# Power_Board_3790.net
KiCad netlist of a schematic drawn in Altium Designer
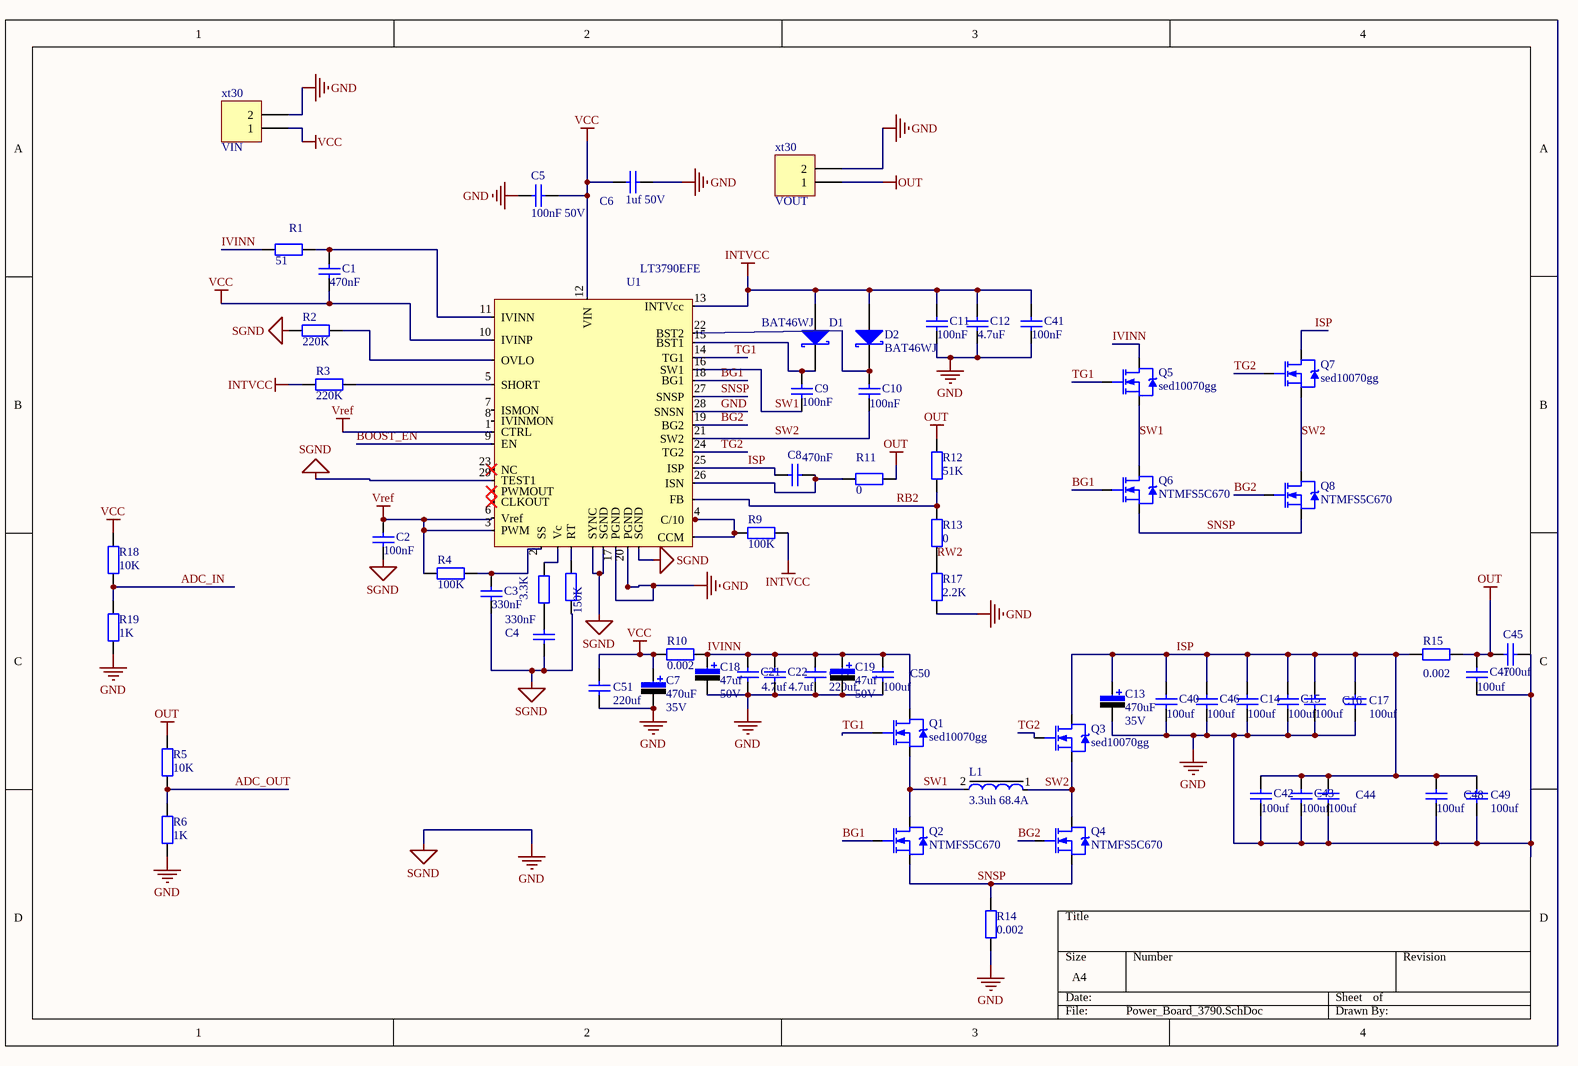
[diagram p0: Power_Board_3790.SchDoc]

(export (version "E")
  (design (tool "Eeschema 10.0.6"))
  (components
    (comp (ref "C1")
      (value "470nF")
      (footprint "c0402")
      (description "无极性电容")
      (fields (field (name "PUBLISHER") "Altium Limited"))
      (libsource (lib "Fszhang") (part "Cap"))
    )
    (comp (ref "C2")
      (value "100nF")
      (footprint "c0402")
      (description "无极性电容")
      (fields (field (name "PUBLISHER") "Altium Limited"))
      (libsource (lib "Fszhang") (part "Cap"))
    )
    (comp (ref "C3")
      (value "330nF")
      (footprint "c0402")
      (description "无极性电容")
      (fields (field (name "PUBLISHER") "Altium Limited"))
      (libsource (lib "Fszhang") (part "Cap"))
    )
    (comp (ref "C4")
      (value "330nF")
      (footprint "c0402")
      (description "无极性电容")
      (fields (field (name "PUBLISHER") "Altium Limited"))
      (libsource (lib "Fszhang") (part "Cap"))
    )
    (comp (ref "C5")
      (value "100nF 50V")
      (footprint "c0402")
      (description "无极性电容")
      (fields (field (name "PUBLISHER") "Altium Limited"))
      (libsource (lib "Fszhang") (part "Cap"))
    )
    (comp (ref "C6")
      (value "1uf 50V")
      (footprint "0805-2")
      (description "无极性电容")
      (fields (field (name "PUBLISHER") "Altium Limited"))
      (libsource (lib "Fszhang") (part "Cap"))
    )
    (comp (ref "C7")
      (value "470uF")
      (footprint "C10X10")
      (description "极性电解电容")
      (fields
        (field (name "VOL") "35V")
        (field (name "Comment") "470uF 35v")
        (field (name "PUBLISHER") "Altium Limited")
      )
      (libsource (lib "Fszhang") (part "Cap Pol"))
    )
    (comp (ref "C8")
      (value "470nF")
      (footprint "c0402")
      (description "无极性电容")
      (fields (field (name "Comment") "470nf") (field (name "PUBLISHER") "Altium Limited"))
      (libsource (lib "Fszhang") (part "Cap"))
    )
    (comp (ref "C9")
      (value "100nF")
      (footprint "c0402")
      (description "无极性电容")
      (fields (field (name "PUBLISHER") "Altium Limited"))
      (libsource (lib "Fszhang") (part "Cap"))
    )
    (comp (ref "C10")
      (value "100nF")
      (footprint "c0402")
      (description "无极性电容")
      (fields (field (name "PUBLISHER") "Altium Limited"))
      (libsource (lib "Fszhang") (part "Cap"))
    )
    (comp (ref "C11")
      (value "100nF")
      (footprint "c0402")
      (description "无极性电容")
      (fields (field (name "PUBLISHER") "Altium Limited"))
      (libsource (lib "Fszhang") (part "Cap"))
    )
    (comp (ref "C12")
      (value "4.7uF")
      (footprint "c0402")
      (description "无极性电容")
      (fields (field (name "PUBLISHER") "Altium Limited"))
      (libsource (lib "Fszhang") (part "Cap"))
    )
    (comp (ref "C13")
      (value "470uF")
      (footprint "C10X10")
      (description "极性电解电容")
      (fields
        (field (name "VOL") "35V")
        (field (name "Comment") "470uf 35V")
        (field (name "PUBLISHER") "Altium Limited")
      )
      (libsource (lib "Fszhang") (part "Cap Pol"))
    )
    (comp (ref "C14")
      (value "100uf")
      (footprint "1210")
      (description "无极性电容")
      (fields (field (name "PUBLISHER") "Altium Limited"))
      (libsource (lib "Fszhang") (part "Cap"))
    )
    (comp (ref "C15")
      (value "100uf")
      (footprint "1210")
      (description "无极性电容")
      (fields (field (name "PUBLISHER") "Altium Limited"))
      (libsource (lib "Fszhang") (part "Cap"))
    )
    (comp (ref "C16")
      (value "100uf")
      (footprint "1210")
      (description "无极性电容")
      (fields (field (name "PUBLISHER") "Altium Limited"))
      (libsource (lib "Fszhang") (part "Cap"))
    )
    (comp (ref "C17")
      (value "100uf")
      (footprint "1210")
      (description "无极性电容")
      (fields (field (name "PUBLISHER") "Altium Limited"))
      (libsource (lib "Fszhang") (part "Cap"))
    )
    (comp (ref "C18")
      (value "47uf")
      (footprint "6.3*7.7MM")
      (description "极性电解电容")
      (fields (field (name "VOL") "50V") (field (name "PUBLISHER") "Altium Limited"))
      (libsource (lib "Fszhang") (part "Cap Pol"))
    )
    (comp (ref "C19")
      (value "47uf")
      (footprint "6.3*7.7MM")
      (description "极性电解电容")
      (fields (field (name "VOL") "50V") (field (name "PUBLISHER") "Altium Limited"))
      (libsource (lib "Fszhang") (part "Cap Pol"))
    )
    (comp (ref "C21")
      (value "4.7uf")
      (footprint "1210")
      (description "无极性电容")
      (fields (field (name "PUBLISHER") "Altium Limited"))
      (libsource (lib "Fszhang") (part "Cap"))
    )
    (comp (ref "C22")
      (value "4.7uf")
      (footprint "1210")
      (description "无极性电容")
      (fields (field (name "PUBLISHER") "Altium Limited"))
      (libsource (lib "Fszhang") (part "Cap"))
    )
    (comp (ref "C39")
      (value "220uf")
      (footprint "1210")
      (description "无极性电容")
      (fields (field (name "PUBLISHER") "Altium Limited"))
      (libsource (lib "Fszhang") (part "Cap"))
    )
    (comp (ref "C40")
      (value "100uf")
      (footprint "1210")
      (description "无极性电容")
      (fields (field (name "PUBLISHER") "Altium Limited"))
      (libsource (lib "Fszhang") (part "Cap"))
    )
    (comp (ref "C41")
      (value "100nF")
      (footprint "c0402")
      (description "无极性电容")
      (fields (field (name "PUBLISHER") "Altium Limited"))
      (libsource (lib "Fszhang") (part "Cap"))
    )
    (comp (ref "C42")
      (value "100uf")
      (footprint "1210")
      (description "无极性电容")
      (fields (field (name "PUBLISHER") "Altium Limited"))
      (libsource (lib "Fszhang") (part "Cap"))
    )
    (comp (ref "C43")
      (value "100uf")
      (footprint "1210")
      (description "无极性电容")
      (fields (field (name "PUBLISHER") "Altium Limited"))
      (libsource (lib "Fszhang") (part "Cap"))
    )
    (comp (ref "C44")
      (value "100uf")
      (footprint "1210")
      (description "无极性电容")
      (fields (field (name "PUBLISHER") "Altium Limited"))
      (libsource (lib "Fszhang") (part "Cap"))
    )
    (comp (ref "C45")
      (value "100uf")
      (footprint "1210")
      (description "无极性电容")
      (fields (field (name "PUBLISHER") "Altium Limited"))
      (libsource (lib "Fszhang") (part "Cap"))
    )
    (comp (ref "C46")
      (value "100uf")
      (footprint "1210")
      (description "无极性电容")
      (fields (field (name "PUBLISHER") "Altium Limited"))
      (libsource (lib "Fszhang") (part "Cap"))
    )
    (comp (ref "C47")
      (value "100uf")
      (footprint "1210")
      (description "无极性电容")
      (fields (field (name "PUBLISHER") "Altium Limited"))
      (libsource (lib "Fszhang") (part "Cap"))
    )
    (comp (ref "C48")
      (value "100uf")
      (footprint "1210")
      (description "无极性电容")
      (fields (field (name "PUBLISHER") "Altium Limited"))
      (libsource (lib "Fszhang") (part "Cap"))
    )
    (comp (ref "C49")
      (value "100uf")
      (footprint "1210")
      (description "无极性电容")
      (fields (field (name "PUBLISHER") "Altium Limited"))
      (libsource (lib "Fszhang") (part "Cap"))
    )
    (comp (ref "C50")
      (value "100uf")
      (footprint "1210")
      (description "无极性电容")
      (fields (field (name "PUBLISHER") "Altium Limited"))
      (libsource (lib "Fszhang") (part "Cap"))
    )
    (comp (ref "C51")
      (value "220uf")
      (footprint "1210")
      (description "无极性电容")
      (fields (field (name "PUBLISHER") "Altium Limited"))
      (libsource (lib "Fszhang") (part "Cap"))
    )
    (comp (ref "D1")
      (value "D-Schottky")
      (footprint "sod323")
      (description "肖特基二极管")
      (fields (field (name "TYPE") "BAT46WJ") (field (name "PUBLISHER") "Altium Limited"))
      (libsource (lib "Fszhang") (part "D-Schottky"))
    )
    (comp (ref "D2")
      (value "D-Schottky")
      (footprint "sod323")
      (description "肖特基二极管")
      (fields (field (name "TYPE") "BAT46WJ") (field (name "PUBLISHER") "Altium Limited"))
      (libsource (lib "Fszhang") (part "D-Schottky"))
    )
    (comp (ref "L1")
      (value "10uH")
      (footprint "SER-2900")
      (description "扁铜线功率电感")
      (fields (field (name "L") "3.3uh 68.4A"))
      (libsource (lib "super_cap") (part "L"))
    )
    (comp (ref "Q1")
      (value "sed10070gg")
      (footprint "pg-tdson-8")
      (description "MOS")
      (fields (field (name "PUBLISHER") "Altium Limited"))
      (libsource (lib "super_cap") (part "NMOS-2"))
    )
    (comp (ref "Q2")
      (value "NTMFS5C670")
      (footprint "pg-tdson-8")
      (description "MOS")
      (fields (field (name "PUBLISHER") "Altium Limited"))
      (libsource (lib "super_cap") (part "NMOS-2"))
    )
    (comp (ref "Q3")
      (value "sed10070gg")
      (footprint "pg-tdson-8")
      (description "MOS")
      (fields (field (name "PUBLISHER") "Altium Limited"))
      (libsource (lib "super_cap") (part "NMOS-2"))
    )
    (comp (ref "Q4")
      (value "NTMFS5C670")
      (footprint "pg-tdson-8")
      (description "MOS")
      (fields (field (name "PUBLISHER") "Altium Limited"))
      (libsource (lib "super_cap") (part "NMOS-2"))
    )
    (comp (ref "Q5")
      (value "sed10070gg")
      (footprint "pg-tdson-8")
      (description "MOS")
      (fields (field (name "PUBLISHER") "Altium Limited"))
      (libsource (lib "super_cap") (part "NMOS-2"))
    )
    (comp (ref "Q6")
      (value "NTMFS5C670")
      (footprint "pg-tdson-8")
      (description "MOS")
      (fields (field (name "PUBLISHER") "Altium Limited"))
      (libsource (lib "super_cap") (part "NMOS-2"))
    )
    (comp (ref "Q7")
      (value "sed10070gg")
      (footprint "pg-tdson-8")
      (description "MOS")
      (fields (field (name "PUBLISHER") "Altium Limited"))
      (libsource (lib "super_cap") (part "NMOS-2"))
    )
    (comp (ref "Q8")
      (value "NTMFS5C670")
      (footprint "pg-tdson-8")
      (description "MOS")
      (fields (field (name "PUBLISHER") "Altium Limited"))
      (libsource (lib "super_cap") (part "NMOS-2"))
    )
    (comp (ref "R1")
      (value "51")
      (footprint "r0402")
      (description "贴片电阻")
      (fields (field (name "PUBLISHER") "Altium Limited"))
      (libsource (lib "") (part "Res1_1"))
    )
    (comp (ref "R2")
      (value "220K")
      (footprint "r0402")
      (description "贴片电阻")
      (fields (field (name "PUBLISHER") "Altium Limited"))
      (libsource (lib "") (part "Res1_1"))
    )
    (comp (ref "R3")
      (value "220K")
      (footprint "r0402")
      (description "贴片电阻")
      (fields (field (name "PUBLISHER") "Altium Limited"))
      (libsource (lib "") (part "Res1_1"))
    )
    (comp (ref "R4")
      (value "100K")
      (footprint "r0402")
      (description "贴片电阻")
      (fields (field (name "PUBLISHER") "Altium Limited"))
      (libsource (lib "") (part "Res1_1"))
    )
    (comp (ref "R5")
      (value "10K")
      (footprint "r0402")
      (description "贴片电阻")
      (fields (field (name "PUBLISHER") "Altium Limited"))
      (libsource (lib "Fszhang") (part "Res1"))
    )
    (comp (ref "R6")
      (value "1K")
      (footprint "r0402")
      (description "贴片电阻")
      (fields (field (name "PUBLISHER") "Altium Limited"))
      (libsource (lib "") (part "Res1_2"))
    )
    (comp (ref "R7")
      (value "3.3K")
      (footprint "r0402")
      (description "贴片电阻")
      (fields (field (name "PUBLISHER") "Altium Limited"))
      (libsource (lib "Fszhang") (part "Res1"))
    )
    (comp (ref "R8")
      (value "150K")
      (footprint "r0402")
      (description "贴片电阻")
      (fields (field (name "PUBLISHER") "Altium Limited"))
      (libsource (lib "Fszhang") (part "Res1"))
    )
    (comp (ref "R9")
      (value "100K")
      (footprint "r0402")
      (description "贴片电阻")
      (fields (field (name "PUBLISHER") "Altium Limited"))
      (libsource (lib "") (part "Res1_1"))
    )
    (comp (ref "R10")
      (value "0.002")
      (footprint "2512")
      (description "贴片电阻")
      (fields (field (name "PUBLISHER") "Altium Limited"))
      (libsource (lib "") (part "Res1_1"))
    )
    (comp (ref "R11")
      (value "0")
      (footprint "r0402")
      (description "贴片电阻")
      (fields (field (name "PUBLISHER") "Altium Limited"))
      (libsource (lib "") (part "Res1_1"))
    )
    (comp (ref "R12")
      (value "51K")
      (footprint "r0402")
      (description "贴片电阻")
      (fields (field (name "PUBLISHER") "Altium Limited"))
      (libsource (lib "Fszhang") (part "Res1"))
    )
    (comp (ref "R13")
      (value "0")
      (footprint "r0402")
      (description "贴片电阻")
      (fields (field (name "PUBLISHER") "Altium Limited"))
      (libsource (lib "") (part "Res1_2"))
    )
    (comp (ref "R14")
      (value "0.002")
      (footprint "2512")
      (description "贴片电阻")
      (fields (field (name "PUBLISHER") "Altium Limited"))
      (libsource (lib "") (part "Res1_2"))
    )
    (comp (ref "R15")
      (value "0.002")
      (footprint "2512")
      (description "贴片电阻")
      (fields (field (name "PUBLISHER") "Altium Limited"))
      (libsource (lib "") (part "Res1_1"))
    )
    (comp (ref "R17")
      (value "2.2K")
      (footprint "r0402")
      (description "贴片电阻")
      (fields (field (name "PUBLISHER") "Altium Limited"))
      (libsource (lib "Fszhang") (part "Res1"))
    )
    (comp (ref "R18")
      (value "10K")
      (footprint "r0402")
      (description "贴片电阻")
      (fields (field (name "PUBLISHER") "Altium Limited"))
      (libsource (lib "Fszhang") (part "Res1"))
    )
    (comp (ref "R19")
      (value "1K")
      (footprint "r0402")
      (description "贴片电阻")
      (fields (field (name "PUBLISHER") "Altium Limited"))
      (libsource (lib "") (part "Res1_2"))
    )
    (comp (ref "U1")
      (value "LT3790EFE")
      (footprint "TSSOP38")
      (description "DC-DC芯片")
      (libsource (lib "super_cap") (part "LT3790"))
    )
    (comp (ref "VIN")
      (value "xt30")
      (footprint "XT30-M")
      (description "接插件")
      (fields (field (name "PUBLISHER") "Altium Limited"))
      (libsource (lib "Fszhang") (part "Header 2"))
    )
    (comp (ref "VOUT")
      (value "xt30")
      (footprint "XT30-M")
      (description "接插件")
      (fields (field (name "PUBLISHER") "Altium Limited"))
      (libsource (lib "Fszhang") (part "Header 2"))
    )
  )
  (nets
    (net (code "1") (name "/ADC_IN") (class "Default")
      (node (ref "R18") (pin "1") (pinfunction "1_1") (pintype "passive"))
      (node (ref "R19") (pin "1") (pinfunction "1_1") (pintype "passive"))
    )
    (net (code "2") (name "/ADC_OUT") (class "Default")
      (node (ref "R5") (pin "1") (pinfunction "1_1") (pintype "passive"))
      (node (ref "R6") (pin "1") (pinfunction "1_1") (pintype "passive"))
    )
    (net (code "3") (name "/BG1") (class "Default")
      (node (ref "Q2") (pin "1") (pinfunction "G_1") (pintype "passive"))
      (node (ref "Q6") (pin "1") (pinfunction "G_1") (pintype "passive"))
      (node (ref "U1") (pin "18") (pinfunction "BG1_18") (pintype "passive"))
    )
    (net (code "4") (name "/BG2") (class "Default")
      (node (ref "Q4") (pin "1") (pinfunction "G_1") (pintype "passive"))
      (node (ref "Q8") (pin "1") (pinfunction "G_1") (pintype "passive"))
      (node (ref "U1") (pin "19") (pinfunction "BG2_19") (pintype "passive"))
    )
    (net (code "5") (name "/BOOST_EN") (class "Default")
      (node (ref "U1") (pin "9") (pinfunction "EN_9") (pintype "passive"))
    )
    (net (code "6") (name "/ISP") (class "Default")
      (node (ref "C13") (pin "1") (pinfunction "1_1") (pintype "passive"))
      (node (ref "C14") (pin "2") (pinfunction "2_2") (pintype "passive"))
      (node (ref "C15") (pin "2") (pinfunction "2_2") (pintype "passive"))
      (node (ref "C16") (pin "2") (pinfunction "2_2") (pintype "passive"))
      (node (ref "C17") (pin "2") (pinfunction "2_2") (pintype "passive"))
      (node (ref "C40") (pin "2") (pinfunction "2_2") (pintype "passive"))
      (node (ref "C42") (pin "2") (pinfunction "2_2") (pintype "passive"))
      (node (ref "C43") (pin "2") (pinfunction "2_2") (pintype "passive"))
      (node (ref "C44") (pin "2") (pinfunction "2_2") (pintype "passive"))
      (node (ref "C46") (pin "2") (pinfunction "2_2") (pintype "passive"))
      (node (ref "C48") (pin "2") (pinfunction "2_2") (pintype "passive"))
      (node (ref "C49") (pin "2") (pinfunction "2_2") (pintype "passive"))
      (node (ref "C8") (pin "2") (pinfunction "2_2") (pintype "passive"))
      (node (ref "Q3") (pin "2") (pinfunction "D_2") (pintype "passive"))
      (node (ref "Q7") (pin "2") (pinfunction "D_2") (pintype "passive"))
      (node (ref "R15") (pin "1") (pinfunction "1_1") (pintype "passive"))
      (node (ref "U1") (pin "25") (pinfunction "ISP_25") (pintype "passive"))
    )
    (net (code "7") (name "/IVINN") (class "Default")
      (node (ref "C18") (pin "1") (pinfunction "1_1") (pintype "passive"))
      (node (ref "C19") (pin "1") (pinfunction "1_1") (pintype "passive"))
      (node (ref "C21") (pin "2") (pinfunction "2_2") (pintype "passive"))
      (node (ref "C22") (pin "2") (pinfunction "2_2") (pintype "passive"))
      (node (ref "C39") (pin "2") (pinfunction "2_2") (pintype "passive"))
      (node (ref "C50") (pin "2") (pinfunction "2_2") (pintype "passive"))
      (node (ref "Q1") (pin "2") (pinfunction "D_2") (pintype "passive"))
      (node (ref "Q5") (pin "2") (pinfunction "D_2") (pintype "passive"))
      (node (ref "R1") (pin "1") (pinfunction "1_1") (pintype "passive"))
      (node (ref "R10") (pin "2") (pinfunction "2_2") (pintype "passive"))
    )
    (net (code "8") (name "/RB2") (class "Default")
      (node (ref "R12") (pin "1") (pinfunction "1_1") (pintype "passive"))
      (node (ref "R13") (pin "1") (pinfunction "1_1") (pintype "passive"))
      (node (ref "U1") (pin "37") (pinfunction "FB_37") (pintype "passive"))
    )
    (net (code "9") (name "/RW2") (class "Default")
      (node (ref "R13") (pin "2") (pinfunction "2_2") (pintype "passive"))
      (node (ref "R17") (pin "2") (pinfunction "2_2") (pintype "passive"))
    )
    (net (code "10") (name "/SNSP") (class "Default")
      (node (ref "Q2") (pin "3") (pinfunction "S_3") (pintype "passive"))
      (node (ref "Q4") (pin "3") (pinfunction "S_3") (pintype "passive"))
      (node (ref "Q6") (pin "3") (pinfunction "S_3") (pintype "passive"))
      (node (ref "Q8") (pin "3") (pinfunction "S_3") (pintype "passive"))
      (node (ref "R14") (pin "1") (pinfunction "1_1") (pintype "passive"))
      (node (ref "U1") (pin "27") (pinfunction "SNSP_27") (pintype "passive"))
    )
    (net (code "11") (name "/SW1") (class "Default")
      (node (ref "C9") (pin "1") (pinfunction "1_1") (pintype "passive"))
      (node (ref "L1") (pin "2") (pinfunction "1_2") (pintype "passive"))
      (node (ref "Q1") (pin "3") (pinfunction "S_3") (pintype "passive"))
      (node (ref "Q2") (pin "2") (pinfunction "D_2") (pintype "passive"))
      (node (ref "Q5") (pin "3") (pinfunction "S_3") (pintype "passive"))
      (node (ref "Q6") (pin "2") (pinfunction "D_2") (pintype "passive"))
      (node (ref "U1") (pin "16") (pinfunction "SW1_16") (pintype "passive"))
    )
    (net (code "12") (name "/SW2") (class "Default")
      (node (ref "C10") (pin "1") (pinfunction "1_1") (pintype "passive"))
      (node (ref "L1") (pin "1") (pinfunction "2_1") (pintype "passive"))
      (node (ref "Q3") (pin "3") (pinfunction "S_3") (pintype "passive"))
      (node (ref "Q4") (pin "2") (pinfunction "D_2") (pintype "passive"))
      (node (ref "Q7") (pin "3") (pinfunction "S_3") (pintype "passive"))
      (node (ref "Q8") (pin "2") (pinfunction "D_2") (pintype "passive"))
      (node (ref "U1") (pin "21") (pinfunction "SW2_21") (pintype "passive"))
    )
    (net (code "13") (name "/TG1") (class "Default")
      (node (ref "Q1") (pin "1") (pinfunction "G_1") (pintype "passive"))
      (node (ref "Q5") (pin "1") (pinfunction "G_1") (pintype "passive"))
      (node (ref "U1") (pin "14") (pinfunction "TG1_14") (pintype "passive"))
    )
    (net (code "14") (name "/TG2") (class "Default")
      (node (ref "Q3") (pin "1") (pinfunction "G_1") (pintype "passive"))
      (node (ref "Q7") (pin "1") (pinfunction "G_1") (pintype "passive"))
      (node (ref "U1") (pin "24") (pinfunction "TG2_24") (pintype "passive"))
    )
    (net (code "15") (name "GND") (class "Default")
      (node (ref "C11") (pin "1") (pinfunction "1_1") (pintype "passive"))
      (node (ref "C12") (pin "1") (pinfunction "1_1") (pintype "passive"))
      (node (ref "C13") (pin "2") (pinfunction "2_2") (pintype "passive"))
      (node (ref "C14") (pin "1") (pinfunction "1_1") (pintype "passive"))
      (node (ref "C15") (pin "1") (pinfunction "1_1") (pintype "passive"))
      (node (ref "C16") (pin "1") (pinfunction "1_1") (pintype "passive"))
      (node (ref "C17") (pin "1") (pinfunction "1_1") (pintype "passive"))
      (node (ref "C18") (pin "2") (pinfunction "2_2") (pintype "passive"))
      (node (ref "C19") (pin "2") (pinfunction "2_2") (pintype "passive"))
      (node (ref "C2") (pin "1") (pinfunction "1_1") (pintype "passive"))
      (node (ref "C21") (pin "1") (pinfunction "1_1") (pintype "passive"))
      (node (ref "C22") (pin "1") (pinfunction "1_1") (pintype "passive"))
      (node (ref "C3") (pin "1") (pinfunction "1_1") (pintype "passive"))
      (node (ref "C39") (pin "1") (pinfunction "1_1") (pintype "passive"))
      (node (ref "C4") (pin "1") (pinfunction "1_1") (pintype "passive"))
      (node (ref "C40") (pin "1") (pinfunction "1_1") (pintype "passive"))
      (node (ref "C41") (pin "1") (pinfunction "1_1") (pintype "passive"))
      (node (ref "C42") (pin "1") (pinfunction "1_1") (pintype "passive"))
      (node (ref "C43") (pin "1") (pinfunction "1_1") (pintype "passive"))
      (node (ref "C44") (pin "1") (pinfunction "1_1") (pintype "passive"))
      (node (ref "C45") (pin "2") (pinfunction "2_2") (pintype "passive"))
      (node (ref "C46") (pin "1") (pinfunction "1_1") (pintype "passive"))
      (node (ref "C47") (pin "1") (pinfunction "1_1") (pintype "passive"))
      (node (ref "C48") (pin "1") (pinfunction "1_1") (pintype "passive"))
      (node (ref "C49") (pin "1") (pinfunction "1_1") (pintype "passive"))
      (node (ref "C5") (pin "1") (pinfunction "1_1") (pintype "passive"))
      (node (ref "C50") (pin "1") (pinfunction "1_1") (pintype "passive"))
      (node (ref "C51") (pin "1") (pinfunction "1_1") (pintype "passive"))
      (node (ref "C6") (pin "1") (pinfunction "1_1") (pintype "passive"))
      (node (ref "C7") (pin "2") (pinfunction "2_2") (pintype "passive"))
      (node (ref "R14") (pin "2") (pinfunction "2_2") (pintype "passive"))
      (node (ref "R17") (pin "1") (pinfunction "1_1") (pintype "passive"))
      (node (ref "R19") (pin "2") (pinfunction "2_2") (pintype "passive"))
      (node (ref "R2") (pin "1") (pinfunction "1_1") (pintype "passive"))
      (node (ref "R6") (pin "2") (pinfunction "2_2") (pintype "passive"))
      (node (ref "R8") (pin "1") (pinfunction "1_1") (pintype "passive"))
      (node (ref "U1") (pin "17") (pinfunction "PGND_17") (pintype "passive"))
      (node (ref "U1") (pin "20") (pinfunction "PGND_20") (pintype "passive"))
      (node (ref "U1") (pin "28") (pinfunction "SNSN_28") (pintype "passive"))
      (node (ref "U1") (pin "29") (pinfunction "TEST1_29") (pintype "passive"))
      (node (ref "U1") (pin "30") (pinfunction "SGND_30") (pintype "passive"))
      (node (ref "U1") (pin "34") (pinfunction "SYNC_34") (pintype "passive"))
      (node (ref "U1") (pin "39") (pinfunction "SGND_39") (pintype "passive"))
      (node (ref "VIN") (pin "2") (pinfunction "2_2") (pintype "passive"))
      (node (ref "VOUT") (pin "2") (pinfunction "2_2") (pintype "passive"))
    )
    (net (code "16") (name "INTVCC") (class "Default")
      (node (ref "C11") (pin "2") (pinfunction "2_2") (pintype "passive"))
      (node (ref "C12") (pin "2") (pinfunction "2_2") (pintype "passive"))
      (node (ref "C41") (pin "2") (pinfunction "2_2") (pintype "passive"))
      (node (ref "D1") (pin "1") (pinfunction "A_1") (pintype "passive"))
      (node (ref "D2") (pin "1") (pinfunction "A_1") (pintype "passive"))
      (node (ref "R3") (pin "1") (pinfunction "1_1") (pintype "passive"))
      (node (ref "R9") (pin "2") (pinfunction "2_2") (pintype "passive"))
      (node (ref "U1") (pin "13") (pinfunction "INTVcc_13") (pintype "passive"))
    )
    (net (code "17") (name "Net-(C4-Pad2)") (class "Default")
      (node (ref "C4") (pin "2") (pinfunction "2_2") (pintype "passive"))
      (node (ref "R7") (pin "1") (pinfunction "1_1") (pintype "passive"))
    )
    (net (code "18") (name "Net-(D1-K)") (class "Default")
      (node (ref "C9") (pin "2") (pinfunction "2_2") (pintype "passive"))
      (node (ref "D1") (pin "2") (pinfunction "K_2") (pintype "passive"))
      (node (ref "U1") (pin "15") (pinfunction "BST1_15") (pintype "passive"))
    )
    (net (code "19") (name "Net-(D2-K)") (class "Default")
      (node (ref "C10") (pin "2") (pinfunction "2_2") (pintype "passive"))
      (node (ref "D2") (pin "2") (pinfunction "K_2") (pintype "passive"))
      (node (ref "U1") (pin "22") (pinfunction "BST2_22") (pintype "passive"))
    )
    (net (code "20") (name "Net-(U1-CCM)") (class "Default")
      (node (ref "R9") (pin "1") (pinfunction "1_1") (pintype "passive"))
      (node (ref "U1") (pin "32") (pinfunction "CCM_32") (pintype "passive"))
      (node (ref "U1") (pin "4") (pinfunction "C/10_4") (pintype "passive"))
    )
    (net (code "21") (name "Net-(U1-ISN)") (class "Default")
      (node (ref "C8") (pin "1") (pinfunction "1_1") (pintype "passive"))
      (node (ref "R11") (pin "1") (pinfunction "1_1") (pintype "passive"))
      (node (ref "U1") (pin "26") (pinfunction "ISN_26") (pintype "passive"))
    )
    (net (code "22") (name "Net-(U1-IVINN)") (class "Default")
      (node (ref "C1") (pin "2") (pinfunction "2_2") (pintype "passive"))
      (node (ref "R1") (pin "2") (pinfunction "2_2") (pintype "passive"))
      (node (ref "U1") (pin "11") (pinfunction "IVINN_11") (pintype "passive"))
    )
    (net (code "23") (name "Net-(U1-OVLO)") (class "Default")
      (node (ref "R2") (pin "2") (pinfunction "2_2") (pintype "passive"))
      (node (ref "U1") (pin "38") (pinfunction "OVLO_38") (pintype "passive"))
    )
    (net (code "24") (name "Net-(U1-RT)") (class "Default")
      (node (ref "R8") (pin "2") (pinfunction "2_2") (pintype "passive"))
      (node (ref "U1") (pin "35") (pinfunction "RT_35") (pintype "passive"))
    )
    (net (code "25") (name "Net-(U1-SHORT)") (class "Default")
      (node (ref "R3") (pin "2") (pinfunction "2_2") (pintype "passive"))
      (node (ref "U1") (pin "5") (pinfunction "SHORT_5") (pintype "passive"))
    )
    (net (code "26") (name "Net-(U1-SS)") (class "Default")
      (node (ref "C3") (pin "2") (pinfunction "2_2") (pintype "passive"))
      (node (ref "R4") (pin "2") (pinfunction "2_2") (pintype "passive"))
      (node (ref "U1") (pin "2") (pinfunction "SS_2") (pintype "passive"))
    )
    (net (code "27") (name "Net-(U1-Vc)") (class "Default")
      (node (ref "R7") (pin "2") (pinfunction "2_2") (pintype "passive"))
      (node (ref "U1") (pin "36") (pinfunction "Vc_36") (pintype "passive"))
    )
    (net (code "28") (name "OUT") (class "Default")
      (node (ref "C45") (pin "1") (pinfunction "1_1") (pintype "passive"))
      (node (ref "C47") (pin "2") (pinfunction "2_2") (pintype "passive"))
      (node (ref "R11") (pin "2") (pinfunction "2_2") (pintype "passive"))
      (node (ref "R12") (pin "2") (pinfunction "2_2") (pintype "passive"))
      (node (ref "R15") (pin "2") (pinfunction "2_2") (pintype "passive"))
      (node (ref "R5") (pin "2") (pinfunction "2_2") (pintype "passive"))
      (node (ref "VOUT") (pin "1") (pinfunction "1_1") (pintype "passive"))
    )
    (net (code "29") (name "VCC") (class "Default")
      (node (ref "C1") (pin "1") (pinfunction "1_1") (pintype "passive"))
      (node (ref "C5") (pin "2") (pinfunction "2_2") (pintype "passive"))
      (node (ref "C51") (pin "2") (pinfunction "2_2") (pintype "passive"))
      (node (ref "C6") (pin "2") (pinfunction "2_2") (pintype "passive"))
      (node (ref "C7") (pin "1") (pinfunction "1_1") (pintype "passive"))
      (node (ref "R10") (pin "1") (pinfunction "1_1") (pintype "passive"))
      (node (ref "R18") (pin "2") (pinfunction "2_2") (pintype "passive"))
      (node (ref "U1") (pin "10") (pinfunction "IVINP_10") (pintype "passive"))
      (node (ref "U1") (pin "12") (pinfunction "VIN_12") (pintype "passive"))
      (node (ref "VIN") (pin "1") (pinfunction "1_1") (pintype "passive"))
    )
    (net (code "30") (name "Vref") (class "Default")
      (node (ref "C2") (pin "2") (pinfunction "2_2") (pintype "passive"))
      (node (ref "R4") (pin "1") (pinfunction "1_1") (pintype "passive"))
      (node (ref "U1") (pin "1") (pinfunction "CTRL_1") (pintype "passive"))
      (node (ref "U1") (pin "3") (pinfunction "PWM_3") (pintype "passive"))
      (node (ref "U1") (pin "6") (pinfunction "Vref_6") (pintype "passive"))
    )
    (net (code "31") (name "unconnected-(U1-CLKOUT-Pad33)") (class "Default")
      (node (ref "U1") (pin "33") (pinfunction "CLKOUT_33") (pintype "passive+no_connect"))
    )
    (net (code "32") (name "unconnected-(U1-ISMON-Pad7)") (class "Default")
      (node (ref "U1") (pin "7") (pinfunction "ISMON_7") (pintype "passive"))
    )
    (net (code "33") (name "unconnected-(U1-IVINMON-Pad8)") (class "Default")
      (node (ref "U1") (pin "8") (pinfunction "IVINMON_8") (pintype "passive"))
    )
    (net (code "34") (name "unconnected-(U1-NC-Pad23)") (class "Default")
      (node (ref "U1") (pin "23") (pinfunction "NC_23") (pintype "passive+no_connect"))
    )
    (net (code "35") (name "unconnected-(U1-PWMOUT-Pad31)") (class "Default")
      (node (ref "U1") (pin "31") (pinfunction "PWMOUT_31") (pintype "passive+no_connect"))
    )
  )
)
